# BabyMonitorBuzzer.net
KiCad netlist of a schematic drawn in EAGLE
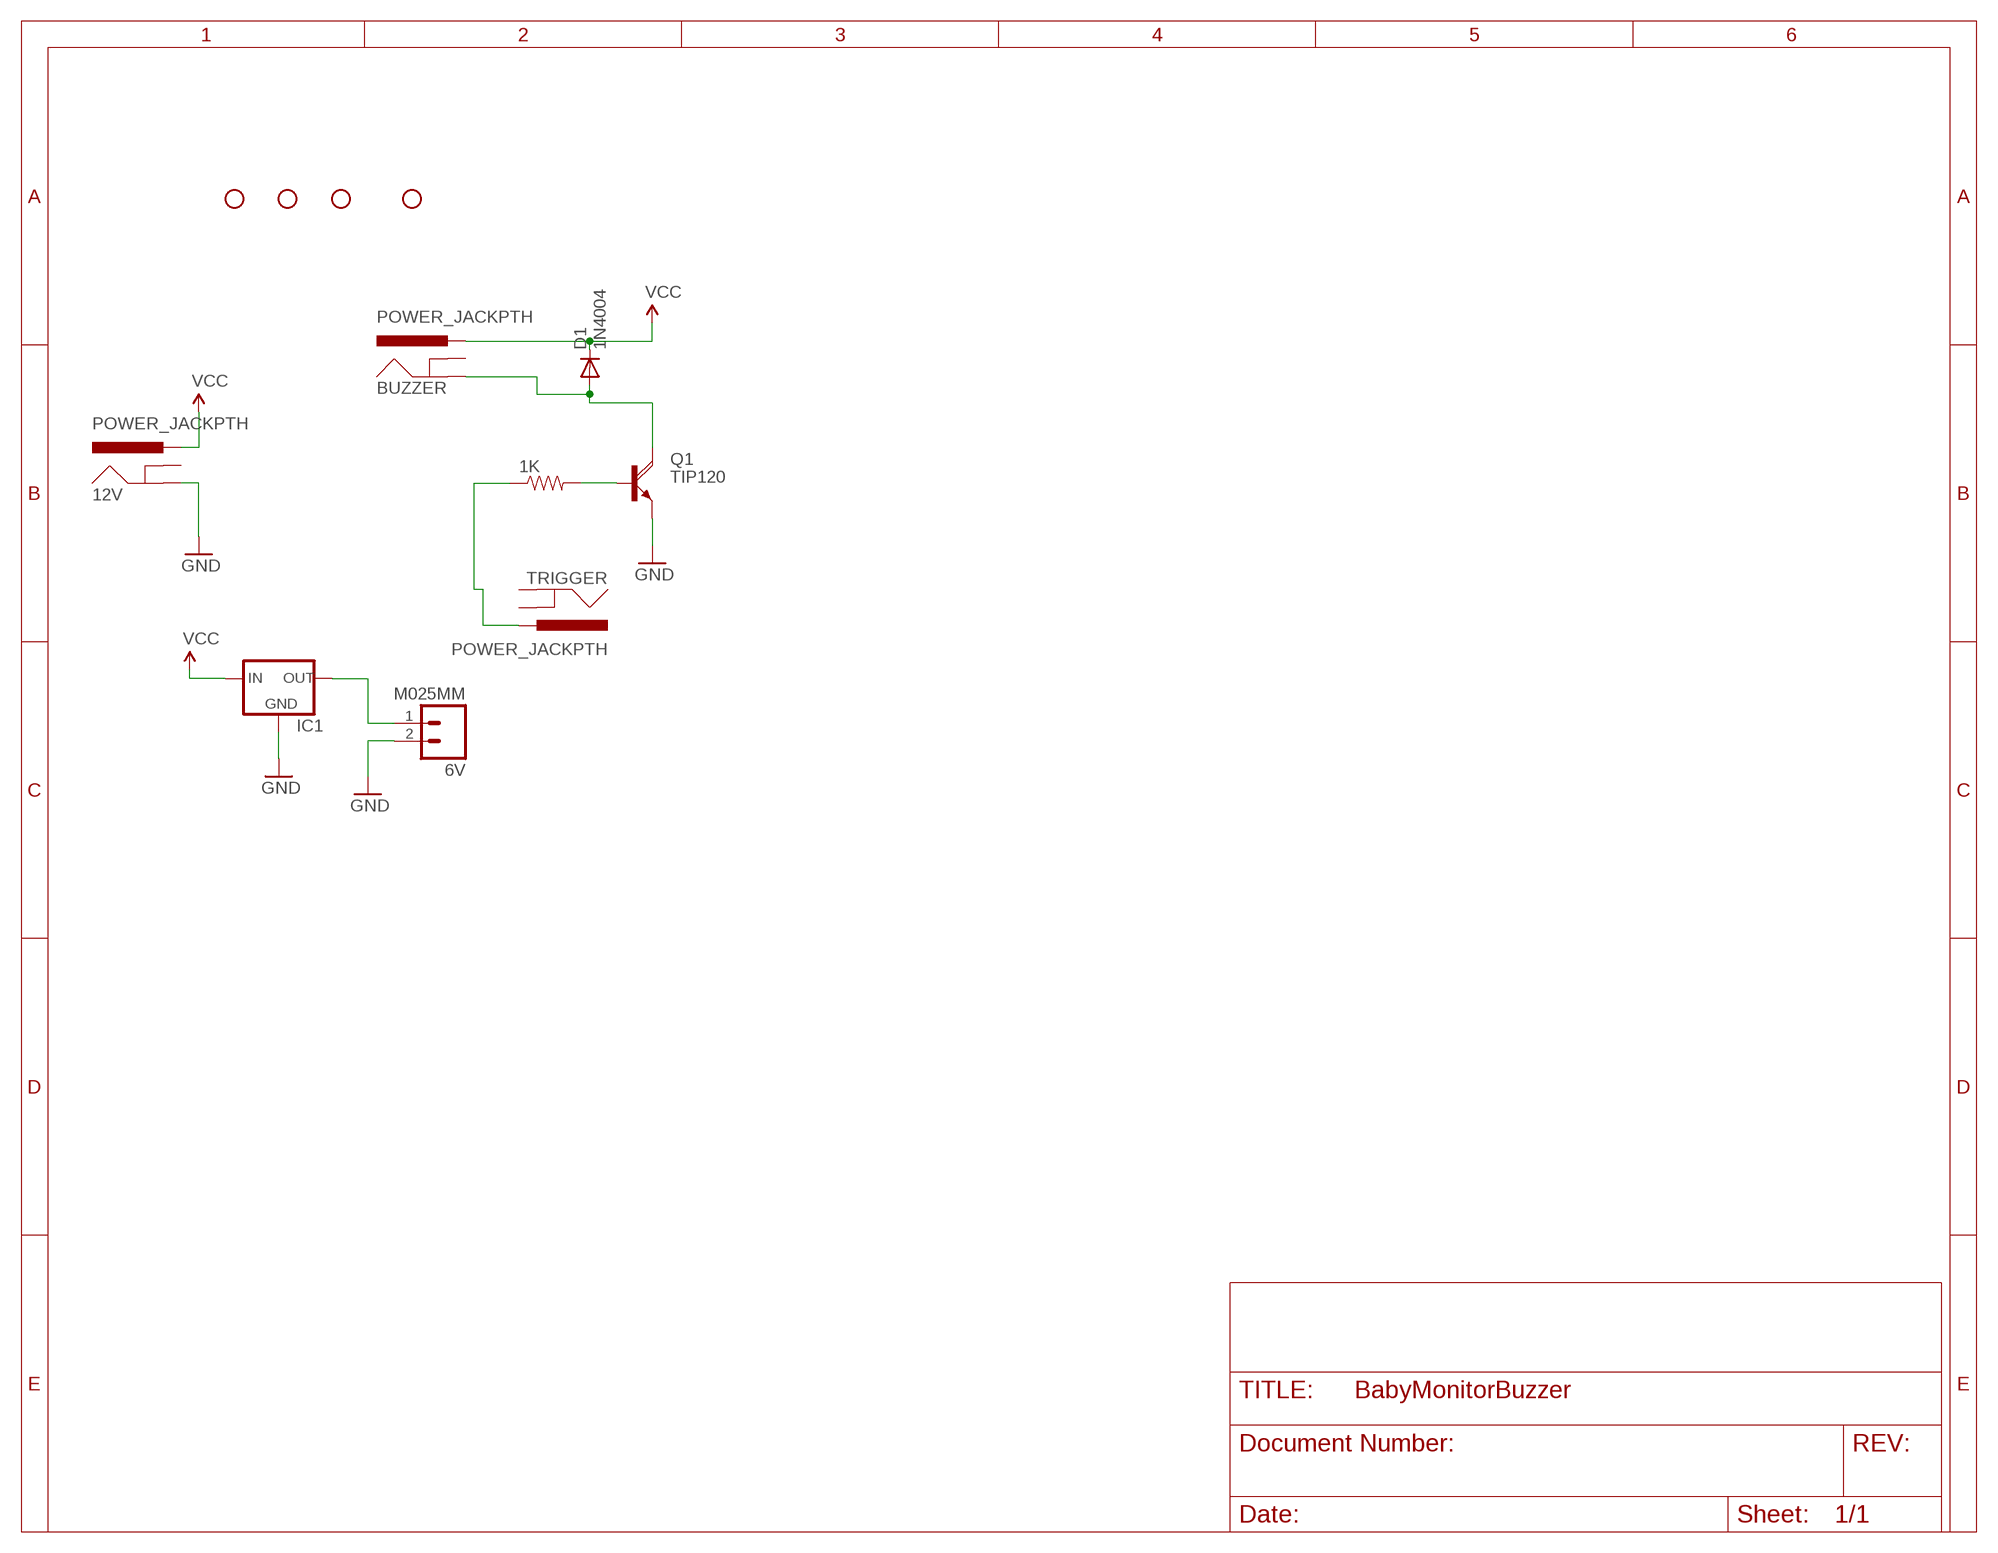
[diagram p0: schematic, sheet 1]

(export (version "E")
  (design (tool "Eeschema 10.0.6"))
  (components
    (comp (ref "1K")
      (value "RESISTORAXIAL-0.3")
      (footprint "eagle-import:AXIAL-0.3")
      (libsource (lib "eagle-import") (part "RESISTORAXIAL-0.3"))
    )
    (comp (ref "6V")
      (value "M025MM")
      (footprint "eagle-import:SCREWTERMINAL-5MM-2")
      (libsource (lib "eagle-import") (part "M025MM"))
    )
    (comp (ref "12V")
      (value "POWER_JACKPTH")
      (footprint "eagle-import:POWER_JACK_PTH")
      (libsource (lib "eagle-import") (part "POWER_JACKPTH"))
    )
    (comp (ref "BUZZER")
      (value "POWER_JACKPTH")
      (footprint "eagle-import:POWER_JACK_PTH")
      (libsource (lib "eagle-import") (part "POWER_JACKPTH"))
    )
    (comp (ref "D1")
      (value "1N4004")
      (footprint "eagle-import:DO41-10")
      (libsource (lib "eagle-import") (part "1N4004"))
    )
    (comp (ref "IC1")
      (value "78XXL")
      (footprint "eagle-import:78XXL")
      (libsource (lib "eagle-import") (part "78XXL"))
    )
    (comp (ref "Q1")
      (value "TIP120")
      (footprint "eagle-import:TO220AH")
      (libsource (lib "eagle-import") (part "TIP120"))
    )
    (comp (ref "STANDOFF1")
      (value "STAND-OFF")
      (footprint "eagle-import:STAND-OFF")
      (libsource (lib "eagle-import") (part "STAND-OFF"))
    )
    (comp (ref "STANDOFF2")
      (value "STAND-OFF")
      (footprint "eagle-import:STAND-OFF")
      (libsource (lib "eagle-import") (part "STAND-OFF"))
    )
    (comp (ref "STANDOFF3")
      (value "STAND-OFF")
      (footprint "eagle-import:STAND-OFF")
      (libsource (lib "eagle-import") (part "STAND-OFF"))
    )
    (comp (ref "STANDOFF4")
      (value "STAND-OFF")
      (footprint "eagle-import:STAND-OFF")
      (libsource (lib "eagle-import") (part "STAND-OFF"))
    )
    (comp (ref "TRIGGER")
      (value "POWER_JACKPTH")
      (footprint "eagle-import:POWER_JACK_PTH")
      (libsource (lib "eagle-import") (part "POWER_JACKPTH"))
    )
  )
  (nets
    (net (code "1") (name "GND") (class "Default")
      (node (ref "12V") (pin "GND") (pinfunction "GND_GND") (pintype "bidirectional"))
      (node (ref "6V") (pin "2") (pinfunction "2_2") (pintype "passive"))
      (node (ref "IC1") (pin "GND") (pinfunction "GND_GND") (pintype "input"))
      (node (ref "Q1") (pin "E") (pinfunction "E_E") (pintype "passive"))
    )
    (net (code "2") (name "Net-(1K-1)") (class "Default")
      (node (ref "1K") (pin "P$1") (pinfunction "1_P$1") (pintype "passive"))
      (node (ref "TRIGGER") (pin "PWR") (pinfunction "PWR_PWR") (pintype "bidirectional"))
    )
    (net (code "3") (name "Net-(1K-2)") (class "Default")
      (node (ref "1K") (pin "P$2") (pinfunction "2_P$2") (pintype "passive"))
      (node (ref "Q1") (pin "B") (pinfunction "B_B") (pintype "passive"))
    )
    (net (code "4") (name "Net-(6V-Pad1)") (class "Default")
      (node (ref "6V") (pin "1") (pinfunction "1_1") (pintype "passive"))
      (node (ref "IC1") (pin "OUT") (pinfunction "OUT_OUT") (pintype "passive"))
    )
    (net (code "5") (name "Net-(BUZZER-PadGND)") (class "Default")
      (node (ref "BUZZER") (pin "GND") (pinfunction "GND_GND") (pintype "bidirectional"))
      (node (ref "D1") (pin "A") (pinfunction "A_A") (pintype "passive"))
      (node (ref "Q1") (pin "C") (pinfunction "C_C") (pintype "passive"))
    )
    (net (code "6") (name "VCC") (class "Default")
      (node (ref "12V") (pin "PWR") (pinfunction "PWR_PWR") (pintype "bidirectional"))
      (node (ref "BUZZER") (pin "PWR") (pinfunction "PWR_PWR") (pintype "bidirectional"))
      (node (ref "D1") (pin "C") (pinfunction "C_C") (pintype "passive"))
      (node (ref "IC1") (pin "IN") (pinfunction "IN_IN") (pintype "input"))
    )
    (net (code "7") (name "unconnected-(12V-PadGNDBREAK)") (class "Default")
      (node (ref "12V") (pin "GNDBREAK") (pinfunction "GNDBREAK_GNDBREAK") (pintype "bidirectional"))
    )
    (net (code "8") (name "unconnected-(BUZZER-PadGNDBREAK)") (class "Default")
      (node (ref "BUZZER") (pin "GNDBREAK") (pinfunction "GNDBREAK_GNDBREAK") (pintype "bidirectional"))
    )
    (net (code "9") (name "unconnected-(TRIGGER-PadGND)") (class "Default")
      (node (ref "TRIGGER") (pin "GND") (pinfunction "GND_GND") (pintype "bidirectional"))
    )
    (net (code "10") (name "unconnected-(TRIGGER-PadGNDBREAK)") (class "Default")
      (node (ref "TRIGGER") (pin "GNDBREAK") (pinfunction "GNDBREAK_GNDBREAK") (pintype "bidirectional"))
    )
  )
)
